# ACBoard.net
KiCad netlist of a schematic drawn in EAGLE
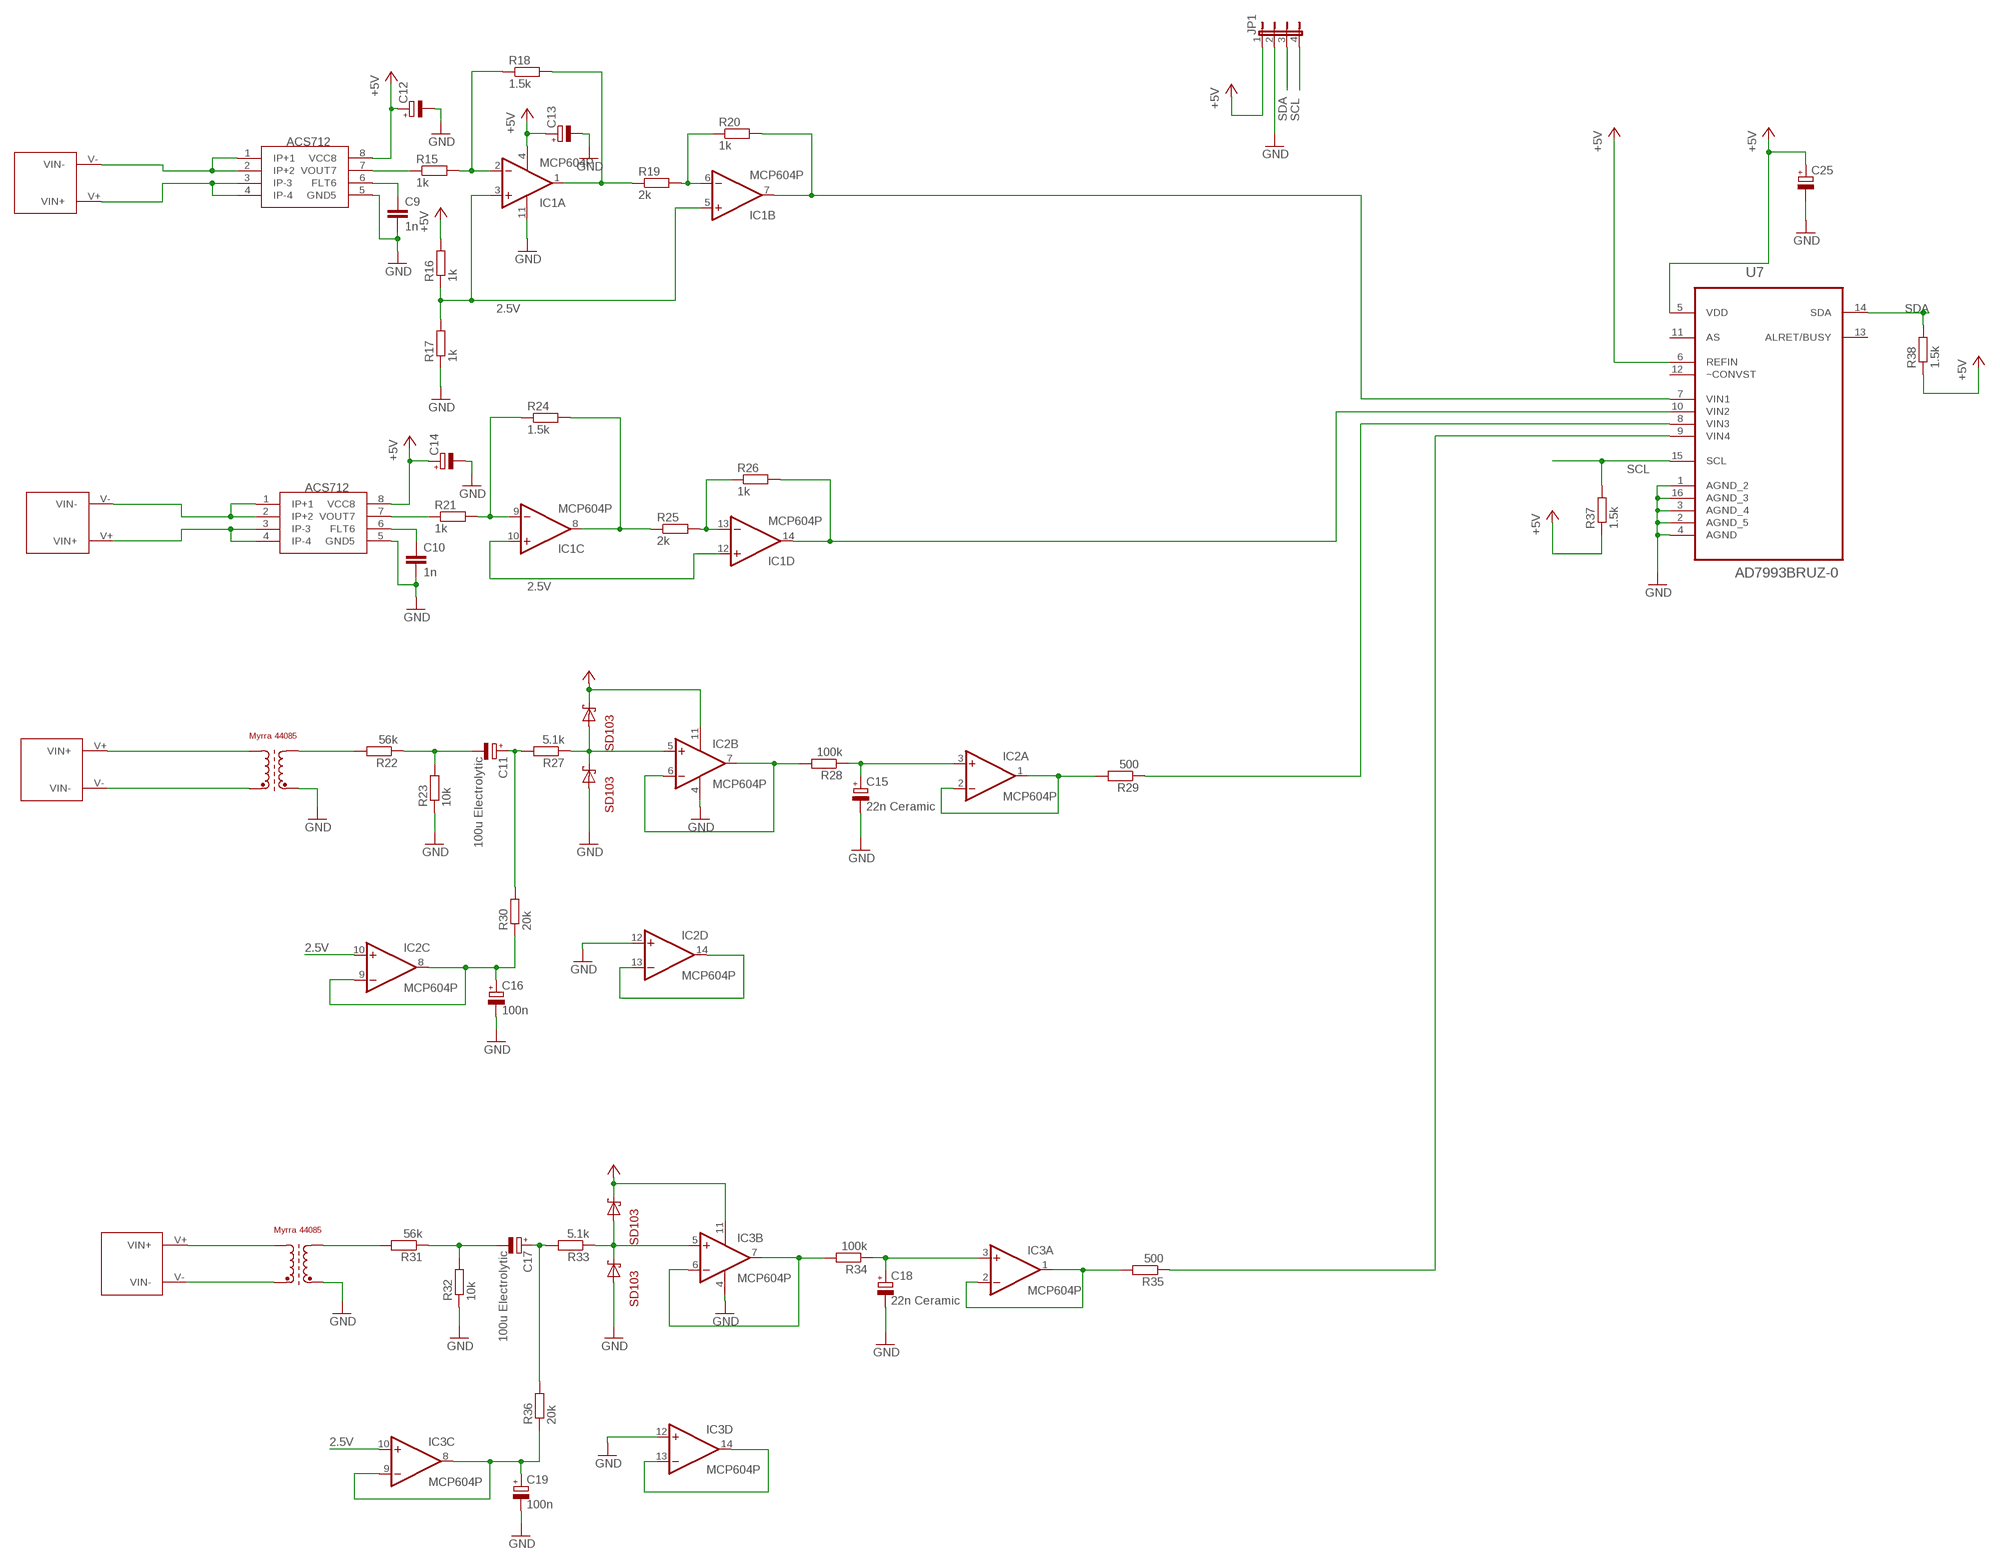
[diagram p0: schematic, sheet 1]

(export (version "E")
  (design (tool "Eeschema 10.0.6"))
  (components
    (comp (ref "C9")
      (value "1n")
      (footprint "eagle-import:C050-050X075")
      (libsource (lib "eagle-import") (part "C-EU050-050X075"))
    )
    (comp (ref "C10")
      (value "1n")
      (footprint "eagle-import:C050-050X075")
      (libsource (lib "eagle-import") (part "C-EU050-050X075"))
    )
    (comp (ref "C11")
      (value "100u Electrolytic")
      (footprint "eagle-import:E2,5-7---100UF")
      (libsource (lib "eagle-import") (part "CPOL1"))
    )
    (comp (ref "C12")
      (value "CPOL1")
      (footprint "eagle-import:E2,5-7---100UF")
      (libsource (lib "eagle-import") (part "CPOL1"))
    )
    (comp (ref "C13")
      (value "CPOL1")
      (footprint "eagle-import:E2,5-7---100UF")
      (libsource (lib "eagle-import") (part "CPOL1"))
    )
    (comp (ref "C14")
      (value "CPOL1")
      (footprint "eagle-import:E2,5-7---100UF")
      (libsource (lib "eagle-import") (part "CPOL1"))
    )
    (comp (ref "C15")
      (value "22n Ceramic")
      (footprint "eagle-import:E2,5-7---100UF")
      (libsource (lib "eagle-import") (part "CPOL1"))
    )
    (comp (ref "C16")
      (value "100n")
      (footprint "eagle-import:E2,5-7---100UF")
      (libsource (lib "eagle-import") (part "CPOL1"))
    )
    (comp (ref "C17")
      (value "100u Electrolytic")
      (footprint "eagle-import:E2,5-7---100UF")
      (libsource (lib "eagle-import") (part "CPOL1"))
    )
    (comp (ref "C18")
      (value "22n Ceramic")
      (footprint "eagle-import:E2,5-7---100UF")
      (libsource (lib "eagle-import") (part "CPOL1"))
    )
    (comp (ref "C19")
      (value "100n")
      (footprint "eagle-import:E2,5-7---100UF")
      (libsource (lib "eagle-import") (part "CPOL1"))
    )
    (comp (ref "C25")
      (value "CPOL-EUE2-4")
      (footprint "eagle-import:E2-4")
      (libsource (lib "eagle-import") (part "CPOL-EUE2-4"))
    )
    (comp (ref "IC1")
      (value "MCP604P")
      (footprint "eagle-import:DIL14")
      (libsource (lib "eagle-import") (part "MCP604P"))
    )
    (comp (ref "IC2")
      (value "MCP604P")
      (footprint "eagle-import:DIL14")
      (libsource (lib "eagle-import") (part "MCP604P"))
    )
    (comp (ref "IC3")
      (value "MCP604P")
      (footprint "eagle-import:DIL14")
      (libsource (lib "eagle-import") (part "MCP604P"))
    )
    (comp (ref "JP1")
      (value "JP4E")
      (footprint "eagle-import:JP4")
      (libsource (lib "eagle-import") (part "JP4E"))
    )
    (comp (ref "R15")
      (value "1k")
      (footprint "eagle-import:0309_12")
      (libsource (lib "eagle-import") (part "R-EU_0309/12"))
    )
    (comp (ref "R16")
      (value "1k")
      (footprint "eagle-import:0309_12")
      (libsource (lib "eagle-import") (part "R-EU_0309/12"))
    )
    (comp (ref "R17")
      (value "1k")
      (footprint "eagle-import:0309_12")
      (libsource (lib "eagle-import") (part "R-EU_0309/12"))
    )
    (comp (ref "R18")
      (value "1.5k")
      (footprint "eagle-import:0309_12")
      (libsource (lib "eagle-import") (part "R-EU_0309/12"))
    )
    (comp (ref "R19")
      (value "2k")
      (footprint "eagle-import:0309_12")
      (libsource (lib "eagle-import") (part "R-EU_0309/12"))
    )
    (comp (ref "R20")
      (value "1k")
      (footprint "eagle-import:0309_12")
      (libsource (lib "eagle-import") (part "R-EU_0309/12"))
    )
    (comp (ref "R21")
      (value "1k")
      (footprint "eagle-import:0309_12")
      (libsource (lib "eagle-import") (part "R-EU_0309/12"))
    )
    (comp (ref "R22")
      (value "56k")
      (footprint "eagle-import:0207_10")
      (libsource (lib "eagle-import") (part "R"))
    )
    (comp (ref "R23")
      (value "10k")
      (footprint "eagle-import:0207_10")
      (libsource (lib "eagle-import") (part "R"))
    )
    (comp (ref "R24")
      (value "1.5k")
      (footprint "eagle-import:0309_12")
      (libsource (lib "eagle-import") (part "R-EU_0309/12"))
    )
    (comp (ref "R25")
      (value "2k")
      (footprint "eagle-import:0309_12")
      (libsource (lib "eagle-import") (part "R-EU_0309/12"))
    )
    (comp (ref "R26")
      (value "1k")
      (footprint "eagle-import:0309_12")
      (libsource (lib "eagle-import") (part "R-EU_0309/12"))
    )
    (comp (ref "R27")
      (value "5.1k")
      (footprint "eagle-import:0207_10")
      (libsource (lib "eagle-import") (part "R"))
    )
    (comp (ref "R28")
      (value "100k")
      (footprint "eagle-import:0207_10")
      (libsource (lib "eagle-import") (part "R"))
    )
    (comp (ref "R29")
      (value "500")
      (footprint "eagle-import:0207_10")
      (libsource (lib "eagle-import") (part "R"))
    )
    (comp (ref "R30")
      (value "20k")
      (footprint "eagle-import:0207_10")
      (libsource (lib "eagle-import") (part "R"))
    )
    (comp (ref "R31")
      (value "56k")
      (footprint "eagle-import:0207_10")
      (libsource (lib "eagle-import") (part "R"))
    )
    (comp (ref "R32")
      (value "10k")
      (footprint "eagle-import:0207_10")
      (libsource (lib "eagle-import") (part "R"))
    )
    (comp (ref "R33")
      (value "5.1k")
      (footprint "eagle-import:0207_10")
      (libsource (lib "eagle-import") (part "R"))
    )
    (comp (ref "R34")
      (value "100k")
      (footprint "eagle-import:0207_10")
      (libsource (lib "eagle-import") (part "R"))
    )
    (comp (ref "R35")
      (value "500")
      (footprint "eagle-import:0207_10")
      (libsource (lib "eagle-import") (part "R"))
    )
    (comp (ref "R36")
      (value "20k")
      (footprint "eagle-import:0207_10")
      (libsource (lib "eagle-import") (part "R"))
    )
    (comp (ref "R37")
      (value "1.5k")
      (footprint "eagle-import:0309_12")
      (libsource (lib "eagle-import") (part "R-EU_0309/12"))
    )
    (comp (ref "R38")
      (value "1.5k")
      (footprint "eagle-import:0309_12")
      (libsource (lib "eagle-import") (part "R-EU_0309/12"))
    )
    (comp (ref "U$1")
      (value "INPUT_VOLTAGE_CONNECTOR")
      (footprint "eagle-import:INPUT_VOLTAGE_CONNECTOR")
      (libsource (lib "eagle-import") (part "INPUT_VOLTAGE_CONNECTOR"))
    )
    (comp (ref "U$2")
      (value "INPUT_VOLTAGE_CONNECTOR")
      (footprint "eagle-import:INPUT_VOLTAGE_CONNECTOR")
      (libsource (lib "eagle-import") (part "INPUT_VOLTAGE_CONNECTOR"))
    )
    (comp (ref "U$3")
      (value "INPUT_VOLTAGE_CONNECTOR")
      (footprint "eagle-import:INPUT_VOLTAGE_CONNECTOR")
      (libsource (lib "eagle-import") (part "INPUT_VOLTAGE_CONNECTOR"))
    )
    (comp (ref "U$4")
      (value "INPUT_VOLTAGE_CONNECTOR")
      (footprint "eagle-import:INPUT_VOLTAGE_CONNECTOR")
      (libsource (lib "eagle-import") (part "INPUT_VOLTAGE_CONNECTOR"))
    )
    (comp (ref "U$9")
      (value "ACS712")
      (footprint "eagle-import:SOIC8")
      (libsource (lib "eagle-import") (part "ACS712"))
    )
    (comp (ref "U$11")
      (value "ACS712")
      (footprint "eagle-import:SOIC8")
      (libsource (lib "eagle-import") (part "ACS712"))
    )
    (comp (ref "U$14")
      (value "MYRRA_4408")
      (footprint "eagle-import:4408")
      (libsource (lib "eagle-import") (part "MYRRA_4408"))
    )
    (comp (ref "U$15")
      (value "SD103A")
      (footprint "eagle-import:D035-10")
      (libsource (lib "eagle-import") (part "SD103A"))
    )
    (comp (ref "U$16")
      (value "SD103A")
      (footprint "eagle-import:D035-10")
      (libsource (lib "eagle-import") (part "SD103A"))
    )
    (comp (ref "U$18")
      (value "MYRRA_4408")
      (footprint "eagle-import:4408")
      (libsource (lib "eagle-import") (part "MYRRA_4408"))
    )
    (comp (ref "U$19")
      (value "SD103A")
      (footprint "eagle-import:D035-10")
      (libsource (lib "eagle-import") (part "SD103A"))
    )
    (comp (ref "U$20")
      (value "SD103A")
      (footprint "eagle-import:D035-10")
      (libsource (lib "eagle-import") (part "SD103A"))
    )
    (comp (ref "U7")
      (value "AD7993BRUZ-0")
      (footprint "eagle-import:SOP65P640X120-16N")
      (libsource (lib "eagle-import") (part "AD7993BRUZ-0"))
    )
  )
  (nets
    (net (code "1") (name "+3V3") (class "Default")
      (node (ref "IC2") (pin "11") (pinfunction "V-_11") (pintype "power_in"))
      (node (ref "IC3") (pin "11") (pinfunction "V-_11") (pintype "power_in"))
      (node (ref "U$15") (pin "C") (pinfunction "C_C") (pintype "passive"))
      (node (ref "U$19") (pin "C") (pinfunction "C_C") (pintype "passive"))
    )
    (net (code "2") (name "+5V") (class "Default")
      (node (ref "C12") (pin "+") (pinfunction "+_+") (pintype "passive"))
      (node (ref "C13") (pin "+") (pinfunction "+_+") (pintype "passive"))
      (node (ref "C14") (pin "+") (pinfunction "+_+") (pintype "passive"))
      (node (ref "C25") (pin "+") (pinfunction "+_+") (pintype "passive"))
      (node (ref "IC1") (pin "4") (pinfunction "V+_4") (pintype "power_in"))
      (node (ref "JP1") (pin "1") (pinfunction "1_1") (pintype "passive"))
      (node (ref "R16") (pin "2") (pinfunction "2_2") (pintype "passive"))
      (node (ref "R37") (pin "1") (pinfunction "1_1") (pintype "passive"))
      (node (ref "R38") (pin "1") (pinfunction "1_1") (pintype "passive"))
      (node (ref "U$11") (pin "8") (pinfunction "VCC8_8") (pintype "power_in"))
      (node (ref "U$9") (pin "8") (pinfunction "VCC8_8") (pintype "power_in"))
      (node (ref "U7") (pin "5") (pinfunction "VDD_5") (pintype "power_in"))
      (node (ref "U7") (pin "6") (pinfunction "REFIN_6") (pintype "input"))
    )
    (net (code "3") (name "/2.5V") (class "Default")
      (node (ref "IC1") (pin "10") (pinfunction "+IN_10") (pintype "input"))
      (node (ref "IC1") (pin "12") (pinfunction "+IN_12") (pintype "input"))
      (node (ref "IC1") (pin "3") (pinfunction "+IN_3") (pintype "input"))
      (node (ref "IC1") (pin "5") (pinfunction "+IN_5") (pintype "input"))
      (node (ref "IC2") (pin "10") (pinfunction "+IN_10") (pintype "input"))
      (node (ref "IC3") (pin "10") (pinfunction "+IN_10") (pintype "input"))
      (node (ref "R16") (pin "1") (pinfunction "1_1") (pintype "passive"))
      (node (ref "R17") (pin "2") (pinfunction "2_2") (pintype "passive"))
    )
    (net (code "4") (name "/SCL") (class "Default")
      (node (ref "JP1") (pin "4") (pinfunction "4_4") (pintype "passive"))
      (node (ref "R37") (pin "2") (pinfunction "2_2") (pintype "passive"))
      (node (ref "U7") (pin "15") (pinfunction "SCL_15") (pintype "input"))
    )
    (net (code "5") (name "/SDA") (class "Default")
      (node (ref "JP1") (pin "3") (pinfunction "3_3") (pintype "passive"))
      (node (ref "R38") (pin "2") (pinfunction "2_2") (pintype "passive"))
      (node (ref "U7") (pin "14") (pinfunction "SDA_14") (pintype "bidirectional"))
    )
    (net (code "6") (name "GND") (class "Default")
      (node (ref "C10") (pin "2") (pinfunction "2_2") (pintype "passive"))
      (node (ref "C12") (pin "-") (pinfunction "-_-") (pintype "passive"))
      (node (ref "C13") (pin "-") (pinfunction "-_-") (pintype "passive"))
      (node (ref "C14") (pin "-") (pinfunction "-_-") (pintype "passive"))
      (node (ref "C15") (pin "-") (pinfunction "-_-") (pintype "passive"))
      (node (ref "C16") (pin "-") (pinfunction "-_-") (pintype "passive"))
      (node (ref "C18") (pin "-") (pinfunction "-_-") (pintype "passive"))
      (node (ref "C19") (pin "-") (pinfunction "-_-") (pintype "passive"))
      (node (ref "C25") (pin "-") (pinfunction "-_-") (pintype "passive"))
      (node (ref "C9") (pin "2") (pinfunction "2_2") (pintype "passive"))
      (node (ref "IC1") (pin "11") (pinfunction "V-_11") (pintype "power_in"))
      (node (ref "IC2") (pin "12") (pinfunction "+IN_12") (pintype "input"))
      (node (ref "IC2") (pin "4") (pinfunction "V+_4") (pintype "power_in"))
      (node (ref "IC3") (pin "12") (pinfunction "+IN_12") (pintype "input"))
      (node (ref "IC3") (pin "4") (pinfunction "V+_4") (pintype "power_in"))
      (node (ref "JP1") (pin "2") (pinfunction "2_2") (pintype "passive"))
      (node (ref "R17") (pin "1") (pinfunction "1_1") (pintype "passive"))
      (node (ref "R23") (pin "1") (pinfunction "1_1") (pintype "passive"))
      (node (ref "R32") (pin "1") (pinfunction "1_1") (pintype "passive"))
      (node (ref "U$11") (pin "5") (pinfunction "GND5_5") (pintype "power_in"))
      (node (ref "U$14") (pin "PIN9") (pinfunction "E2_PIN9") (pintype "passive"))
      (node (ref "U$16") (pin "A") (pinfunction "A_A") (pintype "passive"))
      (node (ref "U$18") (pin "PIN9") (pinfunction "E2_PIN9") (pintype "passive"))
      (node (ref "U$20") (pin "A") (pinfunction "A_A") (pintype "passive"))
      (node (ref "U$9") (pin "5") (pinfunction "GND5_5") (pintype "power_in"))
      (node (ref "U7") (pin "1") (pinfunction "AGND_2_1") (pintype "passive"))
      (node (ref "U7") (pin "16") (pinfunction "AGND_3_16") (pintype "passive"))
      (node (ref "U7") (pin "2") (pinfunction "AGND_5_2") (pintype "passive"))
      (node (ref "U7") (pin "3") (pinfunction "AGND_4_3") (pintype "passive"))
      (node (ref "U7") (pin "4") (pinfunction "AGND_4") (pintype "passive"))
    )
    (net (code "7") (name "Net-(C11-Pad+)") (class "Default")
      (node (ref "C11") (pin "+") (pinfunction "+_+") (pintype "passive"))
      (node (ref "R27") (pin "2") (pinfunction "2_2") (pintype "passive"))
      (node (ref "R30") (pin "2") (pinfunction "2_2") (pintype "passive"))
    )
    (net (code "8") (name "Net-(C11-Pad-)") (class "Default")
      (node (ref "C11") (pin "-") (pinfunction "-_-") (pintype "passive"))
      (node (ref "R22") (pin "1") (pinfunction "1_1") (pintype "passive"))
      (node (ref "R23") (pin "2") (pinfunction "2_2") (pintype "passive"))
    )
    (net (code "9") (name "Net-(C17-Pad+)") (class "Default")
      (node (ref "C17") (pin "+") (pinfunction "+_+") (pintype "passive"))
      (node (ref "R33") (pin "2") (pinfunction "2_2") (pintype "passive"))
      (node (ref "R36") (pin "2") (pinfunction "2_2") (pintype "passive"))
    )
    (net (code "10") (name "Net-(C17-Pad-)") (class "Default")
      (node (ref "C17") (pin "-") (pinfunction "-_-") (pintype "passive"))
      (node (ref "R31") (pin "1") (pinfunction "1_1") (pintype "passive"))
      (node (ref "R32") (pin "2") (pinfunction "2_2") (pintype "passive"))
    )
    (net (code "11") (name "Net-(IC1A--IN)") (class "Default")
      (node (ref "IC1") (pin "2") (pinfunction "-IN_2") (pintype "input"))
      (node (ref "R15") (pin "2") (pinfunction "2_2") (pintype "passive"))
      (node (ref "R18") (pin "1") (pinfunction "1_1") (pintype "passive"))
    )
    (net (code "12") (name "Net-(IC1A-OUT)") (class "Default")
      (node (ref "IC1") (pin "1") (pinfunction "OUT_1") (pintype "output"))
      (node (ref "R18") (pin "2") (pinfunction "2_2") (pintype "passive"))
      (node (ref "R19") (pin "1") (pinfunction "1_1") (pintype "passive"))
    )
    (net (code "13") (name "Net-(IC1B--IN)") (class "Default")
      (node (ref "IC1") (pin "6") (pinfunction "-IN_6") (pintype "input"))
      (node (ref "R19") (pin "2") (pinfunction "2_2") (pintype "passive"))
      (node (ref "R20") (pin "1") (pinfunction "1_1") (pintype "passive"))
    )
    (net (code "14") (name "Net-(IC1B-OUT)") (class "Default")
      (node (ref "IC1") (pin "7") (pinfunction "OUT_7") (pintype "output"))
      (node (ref "R20") (pin "2") (pinfunction "2_2") (pintype "passive"))
      (node (ref "U7") (pin "7") (pinfunction "VIN1_7") (pintype "input"))
    )
    (net (code "15") (name "Net-(IC1C--IN)") (class "Default")
      (node (ref "IC1") (pin "9") (pinfunction "-IN_9") (pintype "input"))
      (node (ref "R21") (pin "2") (pinfunction "2_2") (pintype "passive"))
      (node (ref "R24") (pin "1") (pinfunction "1_1") (pintype "passive"))
    )
    (net (code "16") (name "Net-(IC1C-OUT)") (class "Default")
      (node (ref "IC1") (pin "8") (pinfunction "OUT_8") (pintype "output"))
      (node (ref "R24") (pin "2") (pinfunction "2_2") (pintype "passive"))
      (node (ref "R25") (pin "1") (pinfunction "1_1") (pintype "passive"))
    )
    (net (code "17") (name "Net-(IC1D--IN)") (class "Default")
      (node (ref "IC1") (pin "13") (pinfunction "-IN_13") (pintype "input"))
      (node (ref "R25") (pin "2") (pinfunction "2_2") (pintype "passive"))
      (node (ref "R26") (pin "1") (pinfunction "1_1") (pintype "passive"))
    )
    (net (code "18") (name "Net-(IC1D-OUT)") (class "Default")
      (node (ref "IC1") (pin "14") (pinfunction "OUT_14") (pintype "output"))
      (node (ref "R26") (pin "2") (pinfunction "2_2") (pintype "passive"))
      (node (ref "U7") (pin "10") (pinfunction "VIN2_10") (pintype "input"))
    )
    (net (code "19") (name "Net-(IC2A-+IN)") (class "Default")
      (node (ref "C15") (pin "+") (pinfunction "+_+") (pintype "passive"))
      (node (ref "IC2") (pin "3") (pinfunction "+IN_3") (pintype "input"))
      (node (ref "R28") (pin "1") (pinfunction "1_1") (pintype "passive"))
    )
    (net (code "20") (name "Net-(IC2A--IN)") (class "Default")
      (node (ref "IC2") (pin "1") (pinfunction "OUT_1") (pintype "output"))
      (node (ref "IC2") (pin "2") (pinfunction "-IN_2") (pintype "input"))
      (node (ref "R29") (pin "2") (pinfunction "2_2") (pintype "passive"))
    )
    (net (code "21") (name "Net-(IC2B-+IN)") (class "Default")
      (node (ref "IC2") (pin "5") (pinfunction "+IN_5") (pintype "input"))
      (node (ref "R27") (pin "1") (pinfunction "1_1") (pintype "passive"))
      (node (ref "U$15") (pin "A") (pinfunction "A_A") (pintype "passive"))
      (node (ref "U$16") (pin "C") (pinfunction "C_C") (pintype "passive"))
    )
    (net (code "22") (name "Net-(IC2B--IN)") (class "Default")
      (node (ref "IC2") (pin "6") (pinfunction "-IN_6") (pintype "input"))
      (node (ref "IC2") (pin "7") (pinfunction "OUT_7") (pintype "output"))
      (node (ref "R28") (pin "2") (pinfunction "2_2") (pintype "passive"))
    )
    (net (code "23") (name "Net-(IC2C--IN)") (class "Default")
      (node (ref "C16") (pin "+") (pinfunction "+_+") (pintype "passive"))
      (node (ref "IC2") (pin "8") (pinfunction "OUT_8") (pintype "output"))
      (node (ref "IC2") (pin "9") (pinfunction "-IN_9") (pintype "input"))
      (node (ref "R30") (pin "1") (pinfunction "1_1") (pintype "passive"))
    )
    (net (code "24") (name "Net-(IC2D--IN)") (class "Default")
      (node (ref "IC2") (pin "13") (pinfunction "-IN_13") (pintype "input"))
      (node (ref "IC2") (pin "14") (pinfunction "OUT_14") (pintype "output"))
    )
    (net (code "25") (name "Net-(IC3A-+IN)") (class "Default")
      (node (ref "C18") (pin "+") (pinfunction "+_+") (pintype "passive"))
      (node (ref "IC3") (pin "3") (pinfunction "+IN_3") (pintype "input"))
      (node (ref "R34") (pin "1") (pinfunction "1_1") (pintype "passive"))
    )
    (net (code "26") (name "Net-(IC3A--IN)") (class "Default")
      (node (ref "IC3") (pin "1") (pinfunction "OUT_1") (pintype "output"))
      (node (ref "IC3") (pin "2") (pinfunction "-IN_2") (pintype "input"))
      (node (ref "R35") (pin "2") (pinfunction "2_2") (pintype "passive"))
    )
    (net (code "27") (name "Net-(IC3B-+IN)") (class "Default")
      (node (ref "IC3") (pin "5") (pinfunction "+IN_5") (pintype "input"))
      (node (ref "R33") (pin "1") (pinfunction "1_1") (pintype "passive"))
      (node (ref "U$19") (pin "A") (pinfunction "A_A") (pintype "passive"))
      (node (ref "U$20") (pin "C") (pinfunction "C_C") (pintype "passive"))
    )
    (net (code "28") (name "Net-(IC3B--IN)") (class "Default")
      (node (ref "IC3") (pin "6") (pinfunction "-IN_6") (pintype "input"))
      (node (ref "IC3") (pin "7") (pinfunction "OUT_7") (pintype "output"))
      (node (ref "R34") (pin "2") (pinfunction "2_2") (pintype "passive"))
    )
    (net (code "29") (name "Net-(IC3C--IN)") (class "Default")
      (node (ref "C19") (pin "+") (pinfunction "+_+") (pintype "passive"))
      (node (ref "IC3") (pin "8") (pinfunction "OUT_8") (pintype "output"))
      (node (ref "IC3") (pin "9") (pinfunction "-IN_9") (pintype "input"))
      (node (ref "R36") (pin "1") (pinfunction "1_1") (pintype "passive"))
    )
    (net (code "30") (name "Net-(IC3D--IN)") (class "Default")
      (node (ref "IC3") (pin "13") (pinfunction "-IN_13") (pintype "input"))
      (node (ref "IC3") (pin "14") (pinfunction "OUT_14") (pintype "output"))
    )
    (net (code "31") (name "Net-(U$1-VIN+)") (class "Default")
      (node (ref "U$1") (pin "V+") (pinfunction "VIN+_V+") (pintype "bidirectional"))
      (node (ref "U$14") (pin "PIN5") (pinfunction "A1_PIN5") (pintype "passive"))
    )
    (net (code "32") (name "Net-(U$1-VIN-)") (class "Default")
      (node (ref "U$1") (pin "V-") (pinfunction "VIN-_V-") (pintype "bidirectional"))
      (node (ref "U$14") (pin "PIN1") (pinfunction "E1_PIN1") (pintype "passive"))
    )
    (net (code "33") (name "Net-(U$3-VIN+)") (class "Default")
      (node (ref "U$3") (pin "V+") (pinfunction "VIN+_V+") (pintype "bidirectional"))
      (node (ref "U$9") (pin "3") (pinfunction "IP-3_3") (pintype "bidirectional"))
      (node (ref "U$9") (pin "4") (pinfunction "IP-4_4") (pintype "bidirectional"))
    )
    (net (code "34") (name "Net-(U$3-VIN-)") (class "Default")
      (node (ref "U$3") (pin "V-") (pinfunction "VIN-_V-") (pintype "bidirectional"))
      (node (ref "U$9") (pin "1") (pinfunction "IP+1_1") (pintype "bidirectional"))
      (node (ref "U$9") (pin "2") (pinfunction "IP+2_2") (pintype "bidirectional"))
    )
    (net (code "35") (name "Net-(U$9-FLT6)") (class "Default")
      (node (ref "C9") (pin "1") (pinfunction "1_1") (pintype "passive"))
      (node (ref "U$9") (pin "6") (pinfunction "FLT6_6") (pintype "passive"))
    )
    (net (code "36") (name "Net-(U$9-VOUT7)") (class "Default")
      (node (ref "R15") (pin "1") (pinfunction "1_1") (pintype "passive"))
      (node (ref "U$9") (pin "7") (pinfunction "VOUT7_7") (pintype "output"))
    )
    (net (code "37") (name "Net-(U$11-FLT6)") (class "Default")
      (node (ref "C10") (pin "1") (pinfunction "1_1") (pintype "passive"))
      (node (ref "U$11") (pin "6") (pinfunction "FLT6_6") (pintype "passive"))
    )
    (net (code "38") (name "Net-(U$11-IP+1)") (class "Default")
      (node (ref "U$11") (pin "1") (pinfunction "IP+1_1") (pintype "bidirectional"))
      (node (ref "U$11") (pin "2") (pinfunction "IP+2_2") (pintype "bidirectional"))
      (node (ref "U$2") (pin "V-") (pinfunction "VIN-_V-") (pintype "bidirectional"))
    )
    (net (code "39") (name "Net-(U$11-IP-3)") (class "Default")
      (node (ref "U$11") (pin "3") (pinfunction "IP-3_3") (pintype "bidirectional"))
      (node (ref "U$11") (pin "4") (pinfunction "IP-4_4") (pintype "bidirectional"))
      (node (ref "U$2") (pin "V+") (pinfunction "VIN+_V+") (pintype "bidirectional"))
    )
    (net (code "40") (name "Net-(U$11-VOUT7)") (class "Default")
      (node (ref "R21") (pin "1") (pinfunction "1_1") (pintype "passive"))
      (node (ref "U$11") (pin "7") (pinfunction "VOUT7_7") (pintype "output"))
    )
    (net (code "41") (name "Net-(U$14-A2)") (class "Default")
      (node (ref "R22") (pin "2") (pinfunction "2_2") (pintype "passive"))
      (node (ref "U$14") (pin "PIN7") (pinfunction "A2_PIN7") (pintype "passive"))
    )
    (net (code "42") (name "Net-(U$18-A1)") (class "Default")
      (node (ref "U$18") (pin "PIN5") (pinfunction "A1_PIN5") (pintype "passive"))
      (node (ref "U$4") (pin "V+") (pinfunction "VIN+_V+") (pintype "bidirectional"))
    )
    (net (code "43") (name "Net-(U$18-A2)") (class "Default")
      (node (ref "R31") (pin "2") (pinfunction "2_2") (pintype "passive"))
      (node (ref "U$18") (pin "PIN7") (pinfunction "A2_PIN7") (pintype "passive"))
    )
    (net (code "44") (name "Net-(U$18-E1)") (class "Default")
      (node (ref "U$18") (pin "PIN1") (pinfunction "E1_PIN1") (pintype "passive"))
      (node (ref "U$4") (pin "V-") (pinfunction "VIN-_V-") (pintype "bidirectional"))
    )
    (net (code "45") (name "Net-(U7-VIN3)") (class "Default")
      (node (ref "R29") (pin "1") (pinfunction "1_1") (pintype "passive"))
      (node (ref "U7") (pin "8") (pinfunction "VIN3_8") (pintype "input"))
    )
    (net (code "46") (name "Net-(U7-VIN4)") (class "Default")
      (node (ref "R35") (pin "1") (pinfunction "1_1") (pintype "passive"))
      (node (ref "U7") (pin "9") (pinfunction "VIN4_9") (pintype "input"))
    )
    (net (code "47") (name "unconnected-(U7-ALRET{slash}BUSY-Pad13)") (class "Default")
      (node (ref "U7") (pin "13") (pinfunction "ALRET/BUSY_13") (pintype "output"))
    )
    (net (code "48") (name "unconnected-(U7-AS-Pad11)") (class "Default")
      (node (ref "U7") (pin "11") (pinfunction "AS_11") (pintype "input"))
    )
    (net (code "49") (name "unconnected-(U7-~{CONVST}-Pad12)") (class "Default")
      (node (ref "U7") (pin "12") (pinfunction "~{CONVST}_12") (pintype "input"))
    )
  )
)
